# square.net
KiCad netlist of a schematic drawn in EAGLE
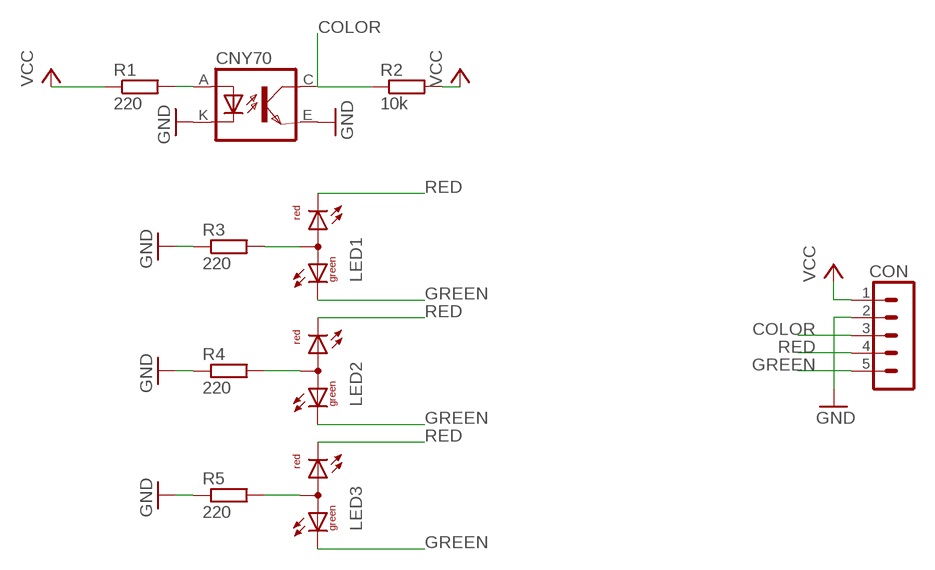
[diagram p0: schematic, sheet 1]

(export (version "E")
  (design (tool "Eeschema 10.0.6"))
  (components
    (comp (ref "CNY70")
      (value "CNY70")
      (footprint "eagle-import:4")
      (libsource (lib "eagle-import") (part "CNY70"))
    )
    (comp (ref "CON")
      (value "CON05")
      (footprint "eagle-import:CON05_2.54MM")
      (libsource (lib "eagle-import") (part "CON05"))
    )
    (comp (ref "LED1")
      (value "L-115WEGW-CA")
      (footprint "eagle-import:DUOLED-A-3MM")
      (libsource (lib "eagle-import") (part "L-115WEGW-CA"))
    )
    (comp (ref "LED2")
      (value "L-115WEGW-CA")
      (footprint "eagle-import:DUOLED-A-3MM")
      (libsource (lib "eagle-import") (part "L-115WEGW-CA"))
    )
    (comp (ref "LED3")
      (value "L-115WEGW-CA")
      (footprint "eagle-import:DUOLED-A-3MM")
      (libsource (lib "eagle-import") (part "L-115WEGW-CA"))
    )
    (comp (ref "R1")
      (value "220")
      (footprint "eagle-import:0204_7")
      (libsource (lib "eagle-import") (part "R-EU_0204/7"))
    )
    (comp (ref "R2")
      (value "10k")
      (footprint "eagle-import:0204_7")
      (libsource (lib "eagle-import") (part "R-EU_0204/7"))
    )
    (comp (ref "R3")
      (value "220")
      (footprint "eagle-import:0204_7")
      (libsource (lib "eagle-import") (part "R-EU_0204/7"))
    )
    (comp (ref "R4")
      (value "220")
      (footprint "eagle-import:0204_7")
      (libsource (lib "eagle-import") (part "R-EU_0204/7"))
    )
    (comp (ref "R5")
      (value "220")
      (footprint "eagle-import:0204_7")
      (libsource (lib "eagle-import") (part "R-EU_0204/7"))
    )
  )
  (nets
    (net (code "1") (name "/COLOR") (class "Default")
      (node (ref "CNY70") (pin "C") (pinfunction "COL_C") (pintype "passive"))
      (node (ref "CON") (pin "3") (pinfunction "3_3") (pintype "passive"))
      (node (ref "R2") (pin "1") (pinfunction "1_1") (pintype "passive"))
    )
    (net (code "2") (name "/GREEN") (class "Default")
      (node (ref "CON") (pin "5") (pinfunction "5_5") (pintype "passive"))
      (node (ref "LED1") (pin "1") (pinfunction "CG_1") (pintype "passive"))
      (node (ref "LED2") (pin "1") (pinfunction "CG_1") (pintype "passive"))
      (node (ref "LED3") (pin "1") (pinfunction "CG_1") (pintype "passive"))
    )
    (net (code "3") (name "/RED") (class "Default")
      (node (ref "CON") (pin "4") (pinfunction "4_4") (pintype "passive"))
      (node (ref "LED1") (pin "3") (pinfunction "CR_3") (pintype "passive"))
      (node (ref "LED2") (pin "3") (pinfunction "CR_3") (pintype "passive"))
      (node (ref "LED3") (pin "3") (pinfunction "CR_3") (pintype "passive"))
    )
    (net (code "4") (name "GND") (class "Default")
      (node (ref "CNY70") (pin "E") (pinfunction "EMI_E") (pintype "passive"))
      (node (ref "CNY70") (pin "K") (pinfunction "C_K") (pintype "passive"))
      (node (ref "CON") (pin "2") (pinfunction "2_2") (pintype "passive"))
      (node (ref "R3") (pin "1") (pinfunction "1_1") (pintype "passive"))
      (node (ref "R4") (pin "1") (pinfunction "1_1") (pintype "passive"))
      (node (ref "R5") (pin "1") (pinfunction "1_1") (pintype "passive"))
    )
    (net (code "5") (name "Net-(CNY70-PadA)") (class "Default")
      (node (ref "CNY70") (pin "A") (pinfunction "A_A") (pintype "passive"))
      (node (ref "R1") (pin "2") (pinfunction "2_2") (pintype "passive"))
    )
    (net (code "6") (name "Net-(LED1-A)") (class "Default")
      (node (ref "LED1") (pin "2") (pinfunction "A_2") (pintype "passive"))
      (node (ref "R3") (pin "2") (pinfunction "2_2") (pintype "passive"))
    )
    (net (code "7") (name "Net-(LED2-A)") (class "Default")
      (node (ref "LED2") (pin "2") (pinfunction "A_2") (pintype "passive"))
      (node (ref "R4") (pin "2") (pinfunction "2_2") (pintype "passive"))
    )
    (net (code "8") (name "Net-(LED3-A)") (class "Default")
      (node (ref "LED3") (pin "2") (pinfunction "A_2") (pintype "passive"))
      (node (ref "R5") (pin "2") (pinfunction "2_2") (pintype "passive"))
    )
    (net (code "9") (name "VCC") (class "Default")
      (node (ref "CON") (pin "1") (pinfunction "1_1") (pintype "passive"))
      (node (ref "R1") (pin "1") (pinfunction "1_1") (pintype "passive"))
      (node (ref "R2") (pin "2") (pinfunction "2_2") (pintype "passive"))
    )
  )
)
